# 3_ECG.net
KiCad netlist of a schematic drawn in Altium Designer
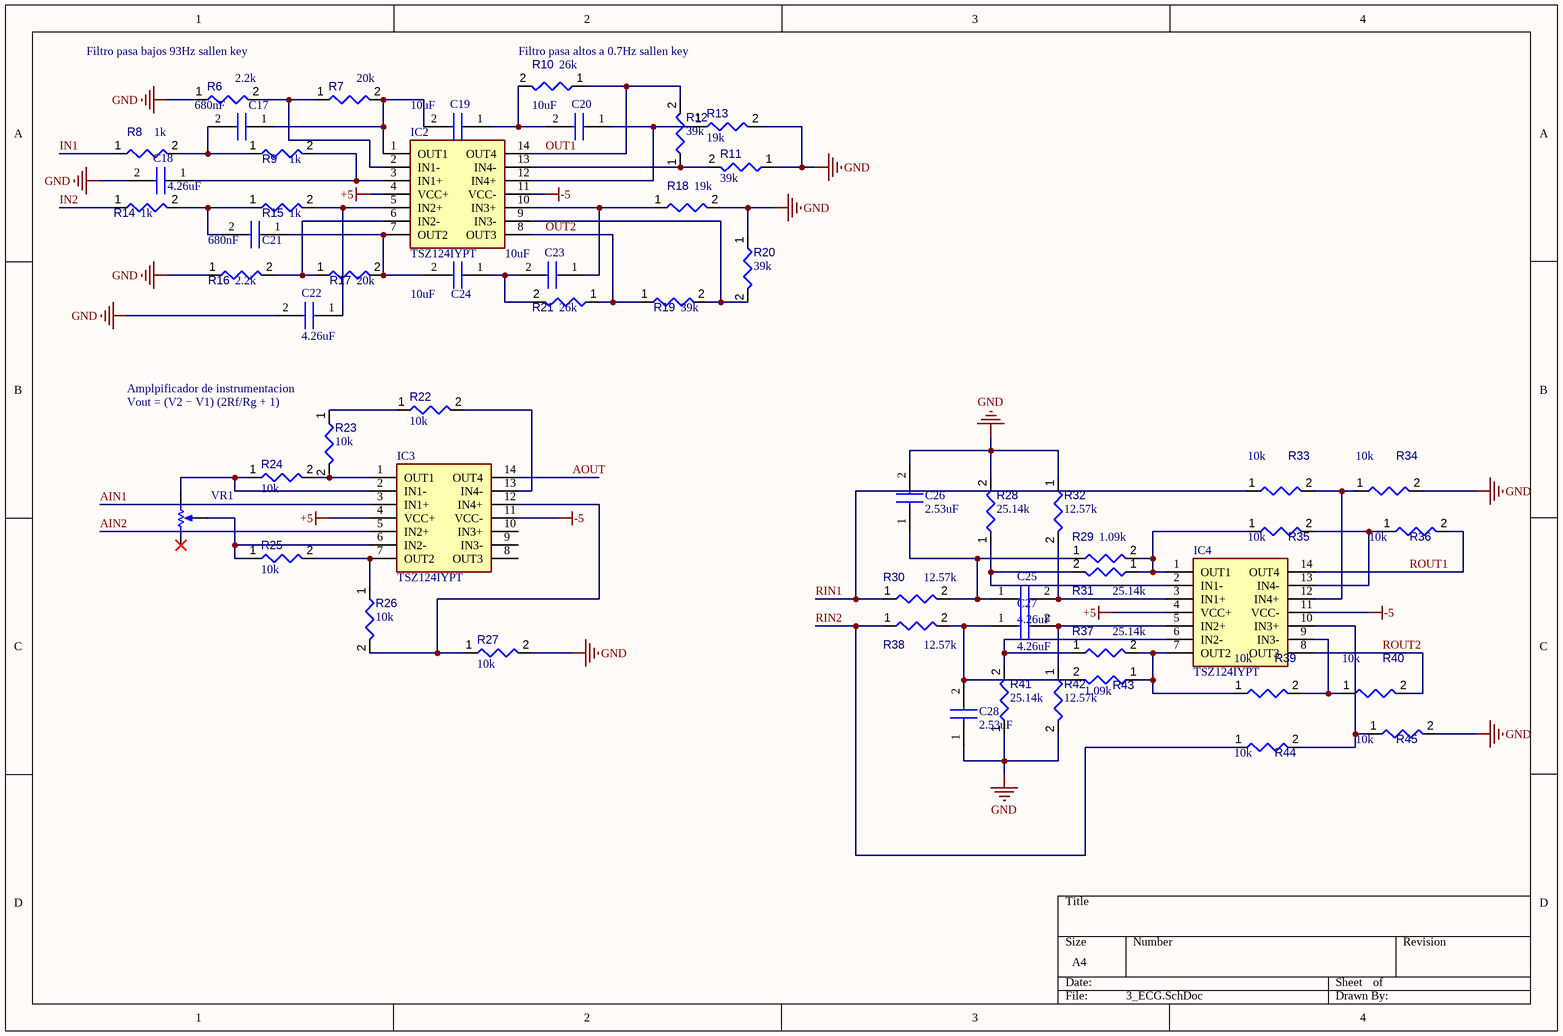
[diagram p0: 3_ECG.SchDoc]

(export (version "E")
  (design (tool "Eeschema 10.0.6"))
  (components
    (comp (ref "C17")
      (value "680nF")
      (footprint "SamacSys:C322C104K1R5TA")
      (description "Capacitor")
      (fields
        (field (name "MANUFACTURER_PART_NUMBER") "C322C104M5U5TA")
        (field (name "MOUSER PART NUMBER") "80-C322C104M5U")
      )
      (libsource (lib "*") (part "C322C104M5U5TA"))
    )
    (comp (ref "C18")
      (value "4.26uF")
      (footprint "SamacSys:C322C104K1R5TA")
      (description "Capacitor")
      (fields
        (field (name "MANUFACTURER_PART_NUMBER") "C322C104M5U5TA")
        (field (name "MOUSER PART NUMBER") "80-C322C104M5U")
      )
      (libsource (lib "*") (part "C322C104M5U5TA"))
    )
    (comp (ref "C19")
      (value "10uF")
      (footprint "SamacSys:C322C104K1R5TA")
      (description "Capacitor")
      (fields
        (field (name "MANUFACTURER_PART_NUMBER") "C322C104M5U5TA")
        (field (name "MOUSER PART NUMBER") "80-C322C104M5U")
      )
      (libsource (lib "*") (part "C322C104M5U5TA"))
    )
    (comp (ref "C20")
      (value "10uF")
      (footprint "SamacSys:C322C104K1R5TA")
      (description "Capacitor")
      (fields
        (field (name "MANUFACTURER_PART_NUMBER") "C322C104M5U5TA")
        (field (name "MOUSER PART NUMBER") "80-C322C104M5U")
      )
      (libsource (lib "*") (part "C322C104M5U5TA"))
    )
    (comp (ref "C21")
      (value "680nF")
      (footprint "SamacSys:C322C104K1R5TA")
      (description "Capacitor")
      (fields
        (field (name "MANUFACTURER_PART_NUMBER") "C322C104M5U5TA")
        (field (name "MOUSER PART NUMBER") "80-C322C104M5U")
      )
      (libsource (lib "*") (part "C322C104M5U5TA"))
    )
    (comp (ref "C22")
      (value "4.26uF")
      (footprint "SamacSys:C322C104K1R5TA")
      (description "Capacitor")
      (fields
        (field (name "MANUFACTURER_PART_NUMBER") "C322C104M5U5TA")
        (field (name "MOUSER PART NUMBER") "80-C322C104M5U")
      )
      (libsource (lib "*") (part "C322C104M5U5TA"))
    )
    (comp (ref "C23")
      (value "10uF")
      (footprint "SamacSys:C322C104K1R5TA")
      (description "Capacitor")
      (fields
        (field (name "MANUFACTURER_PART_NUMBER") "C322C104M5U5TA")
        (field (name "MOUSER PART NUMBER") "80-C322C104M5U")
      )
      (libsource (lib "*") (part "C322C104M5U5TA"))
    )
    (comp (ref "C24")
      (value "10uF")
      (footprint "SamacSys:C322C104K1R5TA")
      (description "Capacitor")
      (fields
        (field (name "MANUFACTURER_PART_NUMBER") "C322C104M5U5TA")
        (field (name "MOUSER PART NUMBER") "80-C322C104M5U")
      )
      (libsource (lib "*") (part "C322C104M5U5TA"))
    )
    (comp (ref "C25")
      (value "4.26uF")
      (footprint "SamacSys:C322C104K1R5TA")
      (description "Capacitor")
      (fields
        (field (name "MANUFACTURER_PART_NUMBER") "C322C104M5U5TA")
        (field (name "MOUSER PART NUMBER") "80-C322C104M5U")
      )
      (libsource (lib "*") (part "C322C104M5U5TA"))
    )
    (comp (ref "C26")
      (value "2.53uF")
      (footprint "SamacSys:C322C104K1R5TA")
      (description "Capacitor")
      (fields
        (field (name "MANUFACTURER_PART_NUMBER") "C322C104M5U5TA")
        (field (name "MOUSER PART NUMBER") "80-C322C104M5U")
      )
      (libsource (lib "*") (part "C322C104M5U5TA"))
    )
    (comp (ref "C27")
      (value "4.26uF")
      (footprint "SamacSys:C322C104K1R5TA")
      (description "Capacitor")
      (fields
        (field (name "MANUFACTURER_PART_NUMBER") "C322C104M5U5TA")
        (field (name "MOUSER PART NUMBER") "80-C322C104M5U")
      )
      (libsource (lib "*") (part "C322C104M5U5TA"))
    )
    (comp (ref "C28")
      (value "2.53uF")
      (footprint "SamacSys:C322C104K1R5TA")
      (description "Capacitor")
      (fields
        (field (name "MANUFACTURER_PART_NUMBER") "C322C104M5U5TA")
        (field (name "MOUSER PART NUMBER") "80-C322C104M5U")
      )
      (libsource (lib "*") (part "C322C104M5U5TA"))
    )
    (comp (ref "IC2")
      (value "TSZ124IYPT")
      (footprint "SamacSys:SOP65P640X120-14N")
      (description "Integrated Circuit")
      (fields (field (name "MOUSER PART NUMBER") "511-TSZ124IYPT"))
      (libsource (lib "*") (part "TSZ124IYPT"))
    )
    (comp (ref "IC3")
      (value "TSZ124IYPT")
      (footprint "SamacSys:SOP65P640X120-14N")
      (description "Integrated Circuit")
      (fields (field (name "MOUSER PART NUMBER") "511-TSZ124IYPT"))
      (libsource (lib "*") (part "TSZ124IYPT"))
    )
    (comp (ref "IC4")
      (value "TSZ124IYPT")
      (footprint "SamacSys:SOP65P640X120-14N")
      (description "Integrated Circuit")
      (fields (field (name "MOUSER PART NUMBER") "511-TSZ124IYPT"))
      (libsource (lib "*") (part "TSZ124IYPT"))
    )
    (comp (ref "R6")
      (value "2.2k")
      (footprint "RESC1608X55X25ML10T15")
      (description "Chip Resistor, 10 KOhm, +/- 1%, 01 W, -55 to 155 degC, 0603 (1608 Metric)")
      (fields (field (name "POWER") "100mW") (field (name "TOLERANCE") "1%"))
      (libsource (lib "Universidad de Guadalajara") (part "RES-2"))
    )
    (comp (ref "R7")
      (value "20k")
      (footprint "RESC1608X55X25ML10T15")
      (description "Chip Resistor, 10 KOhm, +/- 1%, 01 W, -55 to 155 degC, 0603 (1608 Metric)")
      (fields (field (name "POWER") "100mW") (field (name "TOLERANCE") "1%"))
      (libsource (lib "Universidad de Guadalajara") (part "RES-2"))
    )
    (comp (ref "R8")
      (value "1k")
      (footprint "RESC1608X55X25ML10T15")
      (description "Chip Resistor, 10 KOhm, +/- 1%, 01 W, -55 to 155 degC, 0603 (1608 Metric)")
      (fields (field (name "POWER") "100mW") (field (name "TOLERANCE") "1%"))
      (libsource (lib "Universidad de Guadalajara") (part "RES-2"))
    )
    (comp (ref "R9")
      (value "1k")
      (footprint "RESC1608X55X25ML10T15")
      (description "Chip Resistor, 10 KOhm, +/- 1%, 01 W, -55 to 155 degC, 0603 (1608 Metric)")
      (fields (field (name "POWER") "100mW") (field (name "TOLERANCE") "1%"))
      (libsource (lib "Universidad de Guadalajara") (part "RES-2"))
    )
    (comp (ref "R10")
      (value "26k")
      (footprint "RESC1608X55X25ML10T15")
      (description "Chip Resistor, 10 KOhm, +/- 1%, 01 W, -55 to 155 degC, 0603 (1608 Metric)")
      (fields (field (name "POWER") "100mW") (field (name "TOLERANCE") "1%"))
      (libsource (lib "Universidad de Guadalajara") (part "RES-2"))
    )
    (comp (ref "R11")
      (value "39k")
      (footprint "RESC1608X55X25ML10T15")
      (description "Chip Resistor, 10 KOhm, +/- 1%, 01 W, -55 to 155 degC, 0603 (1608 Metric)")
      (fields (field (name "POWER") "100mW") (field (name "TOLERANCE") "1%"))
      (libsource (lib "Universidad de Guadalajara") (part "RES-2"))
    )
    (comp (ref "R12")
      (value "39k")
      (footprint "RESC1608X55X25ML10T15")
      (description "Chip Resistor, 10 KOhm, +/- 1%, 01 W, -55 to 155 degC, 0603 (1608 Metric)")
      (fields (field (name "POWER") "100mW") (field (name "TOLERANCE") "1%"))
      (libsource (lib "Universidad de Guadalajara") (part "RES-2"))
    )
    (comp (ref "R13")
      (value "19k")
      (footprint "RESC1608X55X25ML10T15")
      (description "Chip Resistor, 10 KOhm, +/- 1%, 01 W, -55 to 155 degC, 0603 (1608 Metric)")
      (fields (field (name "POWER") "100mW") (field (name "TOLERANCE") "1%"))
      (libsource (lib "Universidad de Guadalajara") (part "RES-2"))
    )
    (comp (ref "R14")
      (value "1k")
      (footprint "RESC1608X55X25ML10T15")
      (description "Chip Resistor, 10 KOhm, +/- 1%, 01 W, -55 to 155 degC, 0603 (1608 Metric)")
      (fields (field (name "POWER") "100mW") (field (name "TOLERANCE") "1%"))
      (libsource (lib "Universidad de Guadalajara") (part "RES-2"))
    )
    (comp (ref "R15")
      (value "1k")
      (footprint "RESC1608X55X25ML10T15")
      (description "Chip Resistor, 10 KOhm, +/- 1%, 01 W, -55 to 155 degC, 0603 (1608 Metric)")
      (fields (field (name "POWER") "100mW") (field (name "TOLERANCE") "1%"))
      (libsource (lib "Universidad de Guadalajara") (part "RES-2"))
    )
    (comp (ref "R16")
      (value "2.2k")
      (footprint "RESC1608X55X25ML10T15")
      (description "Chip Resistor, 10 KOhm, +/- 1%, 01 W, -55 to 155 degC, 0603 (1608 Metric)")
      (fields (field (name "POWER") "100mW") (field (name "TOLERANCE") "1%"))
      (libsource (lib "Universidad de Guadalajara") (part "RES-2"))
    )
    (comp (ref "R17")
      (value "20k")
      (footprint "RESC1608X55X25ML10T15")
      (description "Chip Resistor, 10 KOhm, +/- 1%, 01 W, -55 to 155 degC, 0603 (1608 Metric)")
      (fields (field (name "POWER") "100mW") (field (name "TOLERANCE") "1%"))
      (libsource (lib "Universidad de Guadalajara") (part "RES-2"))
    )
    (comp (ref "R18")
      (value "19k")
      (footprint "RESC1608X55X25ML10T15")
      (description "Chip Resistor, 10 KOhm, +/- 1%, 01 W, -55 to 155 degC, 0603 (1608 Metric)")
      (fields (field (name "POWER") "100mW") (field (name "TOLERANCE") "1%"))
      (libsource (lib "Universidad de Guadalajara") (part "RES-2"))
    )
    (comp (ref "R19")
      (value "39k")
      (footprint "RESC1608X55X25ML10T15")
      (description "Chip Resistor, 10 KOhm, +/- 1%, 01 W, -55 to 155 degC, 0603 (1608 Metric)")
      (fields (field (name "POWER") "100mW") (field (name "TOLERANCE") "1%"))
      (libsource (lib "Universidad de Guadalajara") (part "RES-2"))
    )
    (comp (ref "R20")
      (value "39k")
      (footprint "RESC1608X55X25ML10T15")
      (description "Chip Resistor, 10 KOhm, +/- 1%, 01 W, -55 to 155 degC, 0603 (1608 Metric)")
      (fields (field (name "POWER") "100mW") (field (name "TOLERANCE") "1%"))
      (libsource (lib "Universidad de Guadalajara") (part "RES-2"))
    )
    (comp (ref "R21")
      (value "26k")
      (footprint "RESC1608X55X25ML10T15")
      (fields (field (name "POWER") "100mW") (field (name "TOLERANCE") "1%"))
      (libsource (lib "Universidad de Guadalajara") (part "RES-2"))
    )
    (comp (ref "R22")
      (value "10k")
      (footprint "RESC1608X55X25ML10T15")
      (description "Chip Resistor, 1 KOhm, +/-1%, 0.1 W, -55 to 155 degC, 0603 (1608 Metric)")
      (fields (field (name "POWER") "100mW") (field (name "TOLERANCE") "1%"))
      (libsource (lib "Universidad de Guadalajara") (part "RES-2"))
    )
    (comp (ref "R23")
      (value "10k")
      (footprint "RESC1608X55X25ML10T15")
      (description "Chip Resistor, 1 KOhm, +/-1%, 0.1 W, -55 to 155 degC, 0603 (1608 Metric)")
      (fields (field (name "POWER") "100mW") (field (name "TOLERANCE") "1%"))
      (libsource (lib "Universidad de Guadalajara") (part "RES-2"))
    )
    (comp (ref "R24")
      (value "10k")
      (footprint "RESC1608X55X25ML10T15")
      (description "Chip Resistor, 1 KOhm, +/-1%, 0.1 W, -55 to 155 degC, 0603 (1608 Metric)")
      (fields (field (name "POWER") "100mW") (field (name "TOLERANCE") "1%"))
      (libsource (lib "Universidad de Guadalajara") (part "RES-2"))
    )
    (comp (ref "R25")
      (value "10k")
      (footprint "RESC1608X55X25ML10T15")
      (description "Chip Resistor, 1 KOhm, +/-1%, 0.1 W, -55 to 155 degC, 0603 (1608 Metric)")
      (fields (field (name "POWER") "100mW") (field (name "TOLERANCE") "1%"))
      (libsource (lib "Universidad de Guadalajara") (part "RES-2"))
    )
    (comp (ref "R26")
      (value "10k")
      (footprint "RESC1608X55X25ML10T15")
      (description "Chip Resistor, 1 KOhm, +/-1%, 0.1 W, -55 to 155 degC, 0603 (1608 Metric)")
      (fields (field (name "POWER") "100mW") (field (name "TOLERANCE") "1%"))
      (libsource (lib "Universidad de Guadalajara") (part "RES-2"))
    )
    (comp (ref "R27")
      (value "10k")
      (footprint "RESC1608X55X25ML10T15")
      (description "Chip Resistor, 1 KOhm, +/-1%, 0.1 W, -55 to 155 degC, 0603 (1608 Metric)")
      (fields (field (name "POWER") "100mW") (field (name "TOLERANCE") "1%"))
      (libsource (lib "Universidad de Guadalajara") (part "RES-2"))
    )
    (comp (ref "R28")
      (value "25.14k")
      (footprint "RESC1608X55X25ML10T15")
      (fields (field (name "POWER") "100mW") (field (name "TOLERANCE") "1%"))
      (libsource (lib "Universidad de Guadalajara") (part "RES-2"))
    )
    (comp (ref "R29")
      (value "1.09k")
      (footprint "RESC1608X55X25ML10T15")
      (description "Chip Resistor, 10 KOhm, +/- 1%, 01 W, -55 to 155 degC, 0603 (1608 Metric)")
      (fields (field (name "POWER") "100mW") (field (name "TOLERANCE") "1%"))
      (libsource (lib "Universidad de Guadalajara") (part "RES-2"))
    )
    (comp (ref "R30")
      (value "12.57k")
      (footprint "RESC1608X55X25ML10T15")
      (description "Chip Resistor, 10 KOhm, +/- 1%, 01 W, -55 to 155 degC, 0603 (1608 Metric)")
      (fields (field (name "POWER") "100mW") (field (name "TOLERANCE") "1%"))
      (libsource (lib "Universidad de Guadalajara") (part "RES-2"))
    )
    (comp (ref "R31")
      (value "25.14k")
      (footprint "RESC1608X55X25ML10T15")
      (description "Chip Resistor, 10 KOhm, +/- 1%, 01 W, -55 to 155 degC, 0603 (1608 Metric)")
      (fields (field (name "POWER") "100mW") (field (name "TOLERANCE") "1%"))
      (libsource (lib "Universidad de Guadalajara") (part "RES-2"))
    )
    (comp (ref "R32")
      (value "12.57k")
      (footprint "RESC1608X55X25ML10T15")
      (description "Chip Resistor, 10 KOhm, +/- 1%, 01 W, -55 to 155 degC, 0603 (1608 Metric)")
      (fields (field (name "POWER") "100mW") (field (name "TOLERANCE") "1%"))
      (libsource (lib "Universidad de Guadalajara") (part "RES-2"))
    )
    (comp (ref "R33")
      (value "10k")
      (footprint "RESC1608X55X25ML10T15")
      (description "Chip Resistor, 10 KOhm, +/- 1%, 01 W, -55 to 155 degC, 0603 (1608 Metric)")
      (fields (field (name "POWER") "100mW") (field (name "TOLERANCE") "1%"))
      (libsource (lib "Universidad de Guadalajara") (part "RES-2"))
    )
    (comp (ref "R34")
      (value "10k")
      (footprint "RESC1608X55X25ML10T15")
      (description "Chip Resistor, 10 KOhm, +/- 1%, 01 W, -55 to 155 degC, 0603 (1608 Metric)")
      (fields (field (name "POWER") "100mW") (field (name "TOLERANCE") "1%"))
      (libsource (lib "Universidad de Guadalajara") (part "RES-2"))
    )
    (comp (ref "R35")
      (value "10k")
      (footprint "RESC1608X55X25ML10T15")
      (description "Chip Resistor, 10 KOhm, +/- 1%, 01 W, -55 to 155 degC, 0603 (1608 Metric)")
      (fields (field (name "POWER") "100mW") (field (name "TOLERANCE") "1%"))
      (libsource (lib "Universidad de Guadalajara") (part "RES-2"))
    )
    (comp (ref "R36")
      (value "10k")
      (footprint "RESC1608X55X25ML10T15")
      (description "Chip Resistor, 10 KOhm, +/- 1%, 01 W, -55 to 155 degC, 0603 (1608 Metric)")
      (fields (field (name "POWER") "100mW") (field (name "TOLERANCE") "1%"))
      (libsource (lib "Universidad de Guadalajara") (part "RES-2"))
    )
    (comp (ref "R37")
      (value "25.14k")
      (footprint "RESC1608X55X25ML10T15")
      (description "Chip Resistor, 10 KOhm, +/- 1%, 01 W, -55 to 155 degC, 0603 (1608 Metric)")
      (fields (field (name "POWER") "100mW") (field (name "TOLERANCE") "1%"))
      (libsource (lib "Universidad de Guadalajara") (part "RES-2"))
    )
    (comp (ref "R38")
      (value "12.57k")
      (footprint "RESC1608X55X25ML10T15")
      (description "Chip Resistor, 10 KOhm, +/- 1%, 01 W, -55 to 155 degC, 0603 (1608 Metric)")
      (fields (field (name "POWER") "100mW") (field (name "TOLERANCE") "1%"))
      (libsource (lib "Universidad de Guadalajara") (part "RES-2"))
    )
    (comp (ref "R39")
      (value "10k")
      (footprint "RESC1608X55X25ML10T15")
      (description "Chip Resistor, 10 KOhm, +/- 1%, 01 W, -55 to 155 degC, 0603 (1608 Metric)")
      (fields (field (name "POWER") "100mW") (field (name "TOLERANCE") "1%"))
      (libsource (lib "Universidad de Guadalajara") (part "RES-2"))
    )
    (comp (ref "R40")
      (value "10k")
      (footprint "RESC1608X55X25ML10T15")
      (description "Chip Resistor, 10 KOhm, +/- 1%, 01 W, -55 to 155 degC, 0603 (1608 Metric)")
      (fields (field (name "POWER") "100mW") (field (name "TOLERANCE") "1%"))
      (libsource (lib "Universidad de Guadalajara") (part "RES-2"))
    )
    (comp (ref "R41")
      (value "25.14k")
      (footprint "RESC1608X55X25ML10T15")
      (description "Chip Resistor, 10 KOhm, +/- 1%, 01 W, -55 to 155 degC, 0603 (1608 Metric)")
      (fields (field (name "POWER") "100mW") (field (name "TOLERANCE") "1%"))
      (libsource (lib "Universidad de Guadalajara") (part "RES-2"))
    )
    (comp (ref "R42")
      (value "12.57k")
      (footprint "RESC1608X55X25ML10T15")
      (description "Chip Resistor, 10 KOhm, +/- 1%, 01 W, -55 to 155 degC, 0603 (1608 Metric)")
      (fields (field (name "POWER") "100mW") (field (name "TOLERANCE") "1%"))
      (libsource (lib "Universidad de Guadalajara") (part "RES-2"))
    )
    (comp (ref "R43")
      (value "1.09k")
      (footprint "RESC1608X55X25ML10T15")
      (description "Chip Resistor, 10 KOhm, +/- 1%, 01 W, -55 to 155 degC, 0603 (1608 Metric)")
      (fields (field (name "POWER") "100mW") (field (name "TOLERANCE") "1%"))
      (libsource (lib "Universidad de Guadalajara") (part "RES-2"))
    )
    (comp (ref "R44")
      (value "10k")
      (footprint "RESC1608X55X25ML10T15")
      (description "Chip Resistor, 10 KOhm, +/- 1%, 01 W, -55 to 155 degC, 0603 (1608 Metric)")
      (fields (field (name "POWER") "100mW") (field (name "TOLERANCE") "1%"))
      (libsource (lib "Universidad de Guadalajara") (part "RES-2"))
    )
    (comp (ref "R45")
      (value "10k")
      (footprint "RESC1608X55X25ML10T15")
      (description "Chip Resistor, 10 KOhm, +/- 1%, 01 W, -55 to 155 degC, 0603 (1608 Metric)")
      (fields (field (name "POWER") "100mW") (field (name "TOLERANCE") "1%"))
      (libsource (lib "Universidad de Guadalajara") (part "RES-2"))
    )
    (comp (ref "VR1")
      (value "3296W-1-103LF")
      (footprint "BOUR-3296W")
      (fields
        (field (name "TOLERANCE") "10%")
        (field (name "POWER") "500mW")
        (field (name "MANUFACTURER") "Bourns")
      )
      (libsource (lib "Universidad de Guadalajara") (part "RES-POT-3"))
    )
  )
  (nets
    (net (code "1") (name "+5") (class "Default")
      (node (ref "IC2") (pin "4") (pinfunction "VCC+_4") (pintype "passive"))
      (node (ref "IC3") (pin "4") (pinfunction "VCC+_4") (pintype "passive"))
      (node (ref "IC4") (pin "4") (pinfunction "VCC+_4") (pintype "passive"))
    )
    (net (code "2") (name "-5") (class "Default")
      (node (ref "IC2") (pin "11") (pinfunction "VCC-_11") (pintype "passive"))
      (node (ref "IC3") (pin "11") (pinfunction "VCC-_11") (pintype "passive"))
      (node (ref "IC4") (pin "11") (pinfunction "VCC-_11") (pintype "passive"))
    )
    (net (code "3") (name "/AIN1") (class "Default")
      (node (ref "IC3") (pin "3") (pinfunction "IN1+_3") (pintype "passive"))
    )
    (net (code "4") (name "/AIN2") (class "Default")
      (node (ref "IC3") (pin "5") (pinfunction "IN2+_5") (pintype "passive"))
    )
    (net (code "5") (name "/AOUT") (class "Default")
      (node (ref "IC3") (pin "14") (pinfunction "OUT4_14") (pintype "passive"))
    )
    (net (code "6") (name "/IN1") (class "Default")
      (node (ref "R8") (pin "1") (pinfunction "1_1") (pintype "passive"))
    )
    (net (code "7") (name "/IN2") (class "Default")
      (node (ref "R14") (pin "1") (pinfunction "1_1") (pintype "passive"))
    )
    (net (code "8") (name "/OUT1") (class "Default")
      (node (ref "IC2") (pin "14") (pinfunction "OUT4_14") (pintype "passive"))
      (node (ref "R10") (pin "1") (pinfunction "1_1") (pintype "passive"))
      (node (ref "R12") (pin "2") (pinfunction "2_2") (pintype "passive"))
    )
    (net (code "9") (name "/OUT2") (class "Default")
      (node (ref "IC2") (pin "8") (pinfunction "OUT3_8") (pintype "passive"))
      (node (ref "R19") (pin "1") (pinfunction "1_1") (pintype "passive"))
      (node (ref "R21") (pin "1") (pinfunction "1_1") (pintype "passive"))
    )
    (net (code "10") (name "/RIN1") (class "Default")
      (node (ref "R30") (pin "1") (pinfunction "1_1") (pintype "passive"))
      (node (ref "R33") (pin "1") (pinfunction "1_1") (pintype "passive"))
    )
    (net (code "11") (name "/RIN2") (class "Default")
      (node (ref "R38") (pin "1") (pinfunction "1_1") (pintype "passive"))
      (node (ref "R44") (pin "1") (pinfunction "1_1") (pintype "passive"))
    )
    (net (code "12") (name "/ROUT1") (class "Default")
      (node (ref "IC4") (pin "14") (pinfunction "OUT4_14") (pintype "passive"))
      (node (ref "R36") (pin "2") (pinfunction "2_2") (pintype "passive"))
    )
    (net (code "13") (name "/ROUT2") (class "Default")
      (node (ref "IC4") (pin "8") (pinfunction "OUT3_8") (pintype "passive"))
      (node (ref "R40") (pin "2") (pinfunction "2_2") (pintype "passive"))
    )
    (net (code "14") (name "GND") (class "Default")
      (node (ref "C18") (pin "2") (pinfunction "-_2") (pintype "passive"))
      (node (ref "C22") (pin "2") (pinfunction "-_2") (pintype "passive"))
      (node (ref "C26") (pin "2") (pinfunction "-_2") (pintype "passive"))
      (node (ref "C28") (pin "1") (pinfunction "+_1") (pintype "passive"))
      (node (ref "R11") (pin "1") (pinfunction "1_1") (pintype "passive"))
      (node (ref "R13") (pin "2") (pinfunction "2_2") (pintype "passive"))
      (node (ref "R16") (pin "1") (pinfunction "1_1") (pintype "passive"))
      (node (ref "R18") (pin "2") (pinfunction "2_2") (pintype "passive"))
      (node (ref "R20") (pin "1") (pinfunction "1_1") (pintype "passive"))
      (node (ref "R27") (pin "2") (pinfunction "2_2") (pintype "passive"))
      (node (ref "R28") (pin "2") (pinfunction "2_2") (pintype "passive"))
      (node (ref "R32") (pin "1") (pinfunction "1_1") (pintype "passive"))
      (node (ref "R34") (pin "2") (pinfunction "2_2") (pintype "passive"))
      (node (ref "R41") (pin "1") (pinfunction "1_1") (pintype "passive"))
      (node (ref "R42") (pin "2") (pinfunction "2_2") (pintype "passive"))
      (node (ref "R45") (pin "2") (pinfunction "2_2") (pintype "passive"))
      (node (ref "R6") (pin "1") (pinfunction "1_1") (pintype "passive"))
    )
    (net (code "15") (name "Net-(C17-+)") (class "Default")
      (node (ref "C17") (pin "1") (pinfunction "+_1") (pintype "passive"))
      (node (ref "C19") (pin "2") (pinfunction "-_2") (pintype "passive"))
      (node (ref "IC2") (pin "1") (pinfunction "OUT1_1") (pintype "passive"))
      (node (ref "R7") (pin "2") (pinfunction "2_2") (pintype "passive"))
    )
    (net (code "16") (name "Net-(C17--)") (class "Default")
      (node (ref "C17") (pin "2") (pinfunction "-_2") (pintype "passive"))
      (node (ref "R8") (pin "2") (pinfunction "2_2") (pintype "passive"))
      (node (ref "R9") (pin "1") (pinfunction "1_1") (pintype "passive"))
    )
    (net (code "17") (name "Net-(C18-+)") (class "Default")
      (node (ref "C18") (pin "1") (pinfunction "+_1") (pintype "passive"))
      (node (ref "IC2") (pin "3") (pinfunction "IN1+_3") (pintype "passive"))
      (node (ref "R9") (pin "2") (pinfunction "2_2") (pintype "passive"))
    )
    (net (code "18") (name "Net-(C19-+)") (class "Default")
      (node (ref "C19") (pin "1") (pinfunction "+_1") (pintype "passive"))
      (node (ref "C20") (pin "2") (pinfunction "-_2") (pintype "passive"))
      (node (ref "R10") (pin "2") (pinfunction "2_2") (pintype "passive"))
    )
    (net (code "19") (name "Net-(C20-+)") (class "Default")
      (node (ref "C20") (pin "1") (pinfunction "+_1") (pintype "passive"))
      (node (ref "IC2") (pin "12") (pinfunction "IN4+_12") (pintype "passive"))
      (node (ref "R13") (pin "1") (pinfunction "1_1") (pintype "passive"))
    )
    (net (code "20") (name "Net-(C21-+)") (class "Default")
      (node (ref "C21") (pin "1") (pinfunction "+_1") (pintype "passive"))
      (node (ref "C24") (pin "2") (pinfunction "-_2") (pintype "passive"))
      (node (ref "IC2") (pin "7") (pinfunction "OUT2_7") (pintype "passive"))
      (node (ref "R17") (pin "2") (pinfunction "2_2") (pintype "passive"))
    )
    (net (code "21") (name "Net-(C21--)") (class "Default")
      (node (ref "C21") (pin "2") (pinfunction "-_2") (pintype "passive"))
      (node (ref "R14") (pin "2") (pinfunction "2_2") (pintype "passive"))
      (node (ref "R15") (pin "1") (pinfunction "1_1") (pintype "passive"))
    )
    (net (code "22") (name "Net-(C22-+)") (class "Default")
      (node (ref "C22") (pin "1") (pinfunction "+_1") (pintype "passive"))
      (node (ref "IC2") (pin "5") (pinfunction "IN2+_5") (pintype "passive"))
      (node (ref "R15") (pin "2") (pinfunction "2_2") (pintype "passive"))
    )
    (net (code "23") (name "Net-(C23-+)") (class "Default")
      (node (ref "C23") (pin "1") (pinfunction "+_1") (pintype "passive"))
      (node (ref "IC2") (pin "10") (pinfunction "IN3+_10") (pintype "passive"))
      (node (ref "R18") (pin "1") (pinfunction "1_1") (pintype "passive"))
    )
    (net (code "24") (name "Net-(C23--)") (class "Default")
      (node (ref "C23") (pin "2") (pinfunction "-_2") (pintype "passive"))
      (node (ref "C24") (pin "1") (pinfunction "+_1") (pintype "passive"))
      (node (ref "R21") (pin "2") (pinfunction "2_2") (pintype "passive"))
    )
    (net (code "25") (name "Net-(C25-+)") (class "Default")
      (node (ref "C25") (pin "1") (pinfunction "+_1") (pintype "passive"))
      (node (ref "C26") (pin "1") (pinfunction "+_1") (pintype "passive"))
      (node (ref "R29") (pin "1") (pinfunction "1_1") (pintype "passive"))
      (node (ref "R30") (pin "2") (pinfunction "2_2") (pintype "passive"))
    )
    (net (code "26") (name "Net-(C25--)") (class "Default")
      (node (ref "C25") (pin "2") (pinfunction "-_2") (pintype "passive"))
      (node (ref "IC4") (pin "3") (pinfunction "IN1+_3") (pintype "passive"))
      (node (ref "R32") (pin "2") (pinfunction "2_2") (pintype "passive"))
    )
    (net (code "27") (name "Net-(C27-+)") (class "Default")
      (node (ref "C27") (pin "1") (pinfunction "+_1") (pintype "passive"))
      (node (ref "C28") (pin "2") (pinfunction "-_2") (pintype "passive"))
      (node (ref "R38") (pin "2") (pinfunction "2_2") (pintype "passive"))
      (node (ref "R43") (pin "2") (pinfunction "2_2") (pintype "passive"))
    )
    (net (code "28") (name "Net-(C27--)") (class "Default")
      (node (ref "C27") (pin "2") (pinfunction "-_2") (pintype "passive"))
      (node (ref "IC4") (pin "5") (pinfunction "IN2+_5") (pintype "passive"))
      (node (ref "R42") (pin "1") (pinfunction "1_1") (pintype "passive"))
    )
    (net (code "29") (name "Net-(IC2-IN1-)") (class "Default")
      (node (ref "IC2") (pin "2") (pinfunction "IN1-_2") (pintype "passive"))
      (node (ref "R6") (pin "2") (pinfunction "2_2") (pintype "passive"))
      (node (ref "R7") (pin "1") (pinfunction "1_1") (pintype "passive"))
    )
    (net (code "30") (name "Net-(IC2-IN2-)") (class "Default")
      (node (ref "IC2") (pin "6") (pinfunction "IN2-_6") (pintype "passive"))
      (node (ref "R16") (pin "2") (pinfunction "2_2") (pintype "passive"))
      (node (ref "R17") (pin "1") (pinfunction "1_1") (pintype "passive"))
    )
    (net (code "31") (name "Net-(IC2-IN3-)") (class "Default")
      (node (ref "IC2") (pin "9") (pinfunction "IN3-_9") (pintype "passive"))
      (node (ref "R19") (pin "2") (pinfunction "2_2") (pintype "passive"))
      (node (ref "R20") (pin "2") (pinfunction "2_2") (pintype "passive"))
    )
    (net (code "32") (name "Net-(IC2-IN4-)") (class "Default")
      (node (ref "IC2") (pin "13") (pinfunction "IN4-_13") (pintype "passive"))
      (node (ref "R11") (pin "2") (pinfunction "2_2") (pintype "passive"))
      (node (ref "R12") (pin "1") (pinfunction "1_1") (pintype "passive"))
    )
    (net (code "33") (name "Net-(IC3-IN1-)") (class "Default")
      (node (ref "IC3") (pin "2") (pinfunction "IN1-_2") (pintype "passive"))
      (node (ref "R24") (pin "1") (pinfunction "1_1") (pintype "passive"))
      (node (ref "VR1") (pin "3") (pinfunction "CW_3") (pintype "passive"))
    )
    (net (code "34") (name "Net-(IC3-IN2-)") (class "Default")
      (node (ref "IC3") (pin "6") (pinfunction "IN2-_6") (pintype "passive"))
      (node (ref "R25") (pin "1") (pinfunction "1_1") (pintype "passive"))
      (node (ref "VR1") (pin "2") (pinfunction "S_2") (pintype "passive"))
    )
    (net (code "35") (name "Net-(IC3-IN4+)") (class "Default")
      (node (ref "IC3") (pin "12") (pinfunction "IN4+_12") (pintype "passive"))
      (node (ref "R26") (pin "2") (pinfunction "2_2") (pintype "passive"))
      (node (ref "R27") (pin "1") (pinfunction "1_1") (pintype "passive"))
    )
    (net (code "36") (name "Net-(IC3-IN4-)") (class "Default")
      (node (ref "IC3") (pin "13") (pinfunction "IN4-_13") (pintype "passive"))
      (node (ref "R22") (pin "2") (pinfunction "2_2") (pintype "passive"))
    )
    (net (code "37") (name "Net-(IC3-OUT1)") (class "Default")
      (node (ref "IC3") (pin "1") (pinfunction "OUT1_1") (pintype "passive"))
      (node (ref "R23") (pin "2") (pinfunction "2_2") (pintype "passive"))
      (node (ref "R24") (pin "2") (pinfunction "2_2") (pintype "passive"))
    )
    (net (code "38") (name "Net-(IC3-OUT2)") (class "Default")
      (node (ref "IC3") (pin "7") (pinfunction "OUT2_7") (pintype "passive"))
      (node (ref "R25") (pin "2") (pinfunction "2_2") (pintype "passive"))
      (node (ref "R26") (pin "1") (pinfunction "1_1") (pintype "passive"))
    )
    (net (code "39") (name "Net-(IC4-IN1-)") (class "Default")
      (node (ref "IC4") (pin "2") (pinfunction "IN1-_2") (pintype "passive"))
      (node (ref "R28") (pin "1") (pinfunction "1_1") (pintype "passive"))
      (node (ref "R31") (pin "2") (pinfunction "2_2") (pintype "passive"))
    )
    (net (code "40") (name "Net-(IC4-IN2-)") (class "Default")
      (node (ref "IC4") (pin "6") (pinfunction "IN2-_6") (pintype "passive"))
      (node (ref "R37") (pin "1") (pinfunction "1_1") (pintype "passive"))
      (node (ref "R41") (pin "2") (pinfunction "2_2") (pintype "passive"))
    )
    (net (code "41") (name "Net-(IC4-IN3+)") (class "Default")
      (node (ref "IC4") (pin "10") (pinfunction "IN3+_10") (pintype "passive"))
      (node (ref "R44") (pin "2") (pinfunction "2_2") (pintype "passive"))
      (node (ref "R45") (pin "1") (pinfunction "1_1") (pintype "passive"))
    )
    (net (code "42") (name "Net-(IC4-IN3-)") (class "Default")
      (node (ref "IC4") (pin "9") (pinfunction "IN3-_9") (pintype "passive"))
      (node (ref "R39") (pin "2") (pinfunction "2_2") (pintype "passive"))
      (node (ref "R40") (pin "1") (pinfunction "1_1") (pintype "passive"))
    )
    (net (code "43") (name "Net-(IC4-IN4+)") (class "Default")
      (node (ref "IC4") (pin "12") (pinfunction "IN4+_12") (pintype "passive"))
      (node (ref "R33") (pin "2") (pinfunction "2_2") (pintype "passive"))
      (node (ref "R34") (pin "1") (pinfunction "1_1") (pintype "passive"))
    )
    (net (code "44") (name "Net-(IC4-IN4-)") (class "Default")
      (node (ref "IC4") (pin "13") (pinfunction "IN4-_13") (pintype "passive"))
      (node (ref "R35") (pin "2") (pinfunction "2_2") (pintype "passive"))
      (node (ref "R36") (pin "1") (pinfunction "1_1") (pintype "passive"))
    )
    (net (code "45") (name "Net-(IC4-OUT1)") (class "Default")
      (node (ref "IC4") (pin "1") (pinfunction "OUT1_1") (pintype "passive"))
      (node (ref "R29") (pin "2") (pinfunction "2_2") (pintype "passive"))
      (node (ref "R31") (pin "1") (pinfunction "1_1") (pintype "passive"))
      (node (ref "R35") (pin "1") (pinfunction "1_1") (pintype "passive"))
    )
    (net (code "46") (name "Net-(IC4-OUT2)") (class "Default")
      (node (ref "IC4") (pin "7") (pinfunction "OUT2_7") (pintype "passive"))
      (node (ref "R37") (pin "2") (pinfunction "2_2") (pintype "passive"))
      (node (ref "R39") (pin "1") (pinfunction "1_1") (pintype "passive"))
      (node (ref "R43") (pin "1") (pinfunction "1_1") (pintype "passive"))
    )
    (net (code "47") (name "Net-(R22-Pad1)") (class "Default")
      (node (ref "R22") (pin "1") (pinfunction "1_1") (pintype "passive"))
      (node (ref "R23") (pin "1") (pinfunction "1_1") (pintype "passive"))
    )
    (net (code "48") (name "unconnected-(IC3-IN3+-Pad10)") (class "Default")
      (node (ref "IC3") (pin "10") (pinfunction "IN3+_10") (pintype "passive"))
    )
    (net (code "49") (name "unconnected-(IC3-IN3--Pad9)") (class "Default")
      (node (ref "IC3") (pin "9") (pinfunction "IN3-_9") (pintype "passive"))
    )
    (net (code "50") (name "unconnected-(IC3-OUT3-Pad8)") (class "Default")
      (node (ref "IC3") (pin "8") (pinfunction "OUT3_8") (pintype "passive"))
    )
    (net (code "51") (name "unconnected-(VR1-CCW-Pad1)") (class "Default")
      (node (ref "VR1") (pin "1") (pinfunction "CCW_1") (pintype "passive+no_connect"))
    )
  )
)
